# Mgmt.net
KiCad netlist of a schematic drawn in Altium Designer
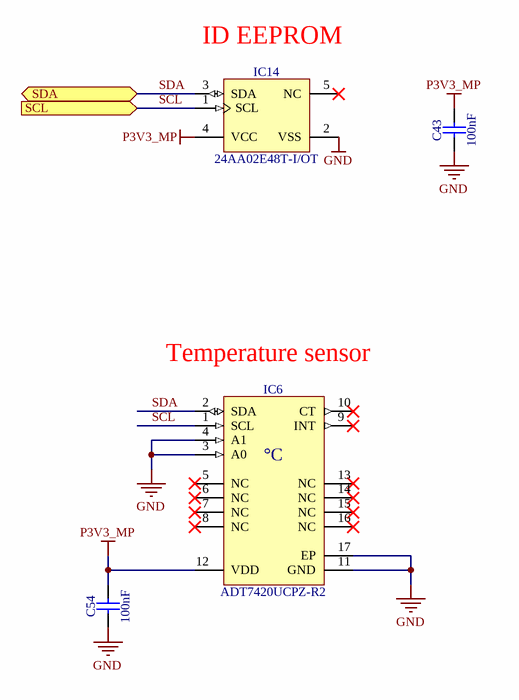
[diagram p0: Mgmt.SchDoc]

(export (version "E")
  (design (tool "Eeschema 10.0.6"))
  (components
    (comp (ref "C43")
      (value "100nF")
      (footprint "CAPC1005X55N")
      (description "Non-polarised capacitor")
      (fields
        (field (name "PART NUMBER") "CC0402_100NF_16V_10%_X5R")
        (field (name "VOLTAGE") "16V")
        (field (name "AUTHOR") "CERN DEM JLC")
      )
      (libsource (lib "Capacitors") (part "Capacitor - non polarized"))
    )
    (comp (ref "C54")
      (value "100nF")
      (footprint "CAPC1005X55N")
      (description "Non-polarised capacitor")
      (fields
        (field (name "PART NUMBER") "CC0402_100NF_16V_10%_X5R")
        (field (name "VOLTAGE") "16V")
        (field (name "AUTHOR") "CERN DEM JLC")
      )
      (libsource (lib "Capacitors") (part "Capacitor - non polarized"))
    )
    (comp (ref "IC6")
      (value "ADT7420UCPZ-R2")
      (footprint "QFN65P400X400X80-17N-S270")
      (description "±0.25°C Accurate, 16-Bit Digital I2C Temperature Sensor")
      (fields (field (name "MANUFACTURER") "ANALOG DEVICES") (field (name "AUTHOR") "CERN DEM JLC"))
      (libsource (lib "ICs And Semiconductors") (part "ADT7420"))
    )
    (comp (ref "IC14")
      (value "24AA02E48T-I/OT")
      (footprint "SOT95P280X145-5N")
      (description "1.7V-5.5V, 2K I2C Serial EEPROM With EUI-48 Node Identity")
      (fields (field (name "MANUFACTURER") "MICROCHIP TECHNOLOGY") (field (name "AUTHOR") "CERN DEM MR"))
      (libsource (lib "ICs And Semiconductors") (part "24AA02E48T-I/OT"))
    )
  )
  (nets
    (net (code "1") (name "/SCL") (class "Default")
      (node (ref "IC14") (pin "1") (pinfunction "SCL_1") (pintype "input"))
      (node (ref "IC6") (pin "1") (pinfunction "SCL_1") (pintype "input"))
    )
    (net (code "2") (name "/SDA") (class "Default")
      (node (ref "IC14") (pin "3") (pinfunction "SDA_3") (pintype "bidirectional"))
      (node (ref "IC6") (pin "2") (pinfunction "SDA_2") (pintype "bidirectional"))
    )
    (net (code "3") (name "GND") (class "Default")
      (node (ref "C43") (pin "1") (pinfunction "1_1") (pintype "passive"))
      (node (ref "C54") (pin "1") (pinfunction "1_1") (pintype "passive"))
      (node (ref "IC14") (pin "2") (pinfunction "VSS_2") (pintype "power_in"))
      (node (ref "IC6") (pin "11") (pinfunction "GND_11") (pintype "power_in"))
      (node (ref "IC6") (pin "17") (pinfunction "EP_17") (pintype "power_in"))
      (node (ref "IC6") (pin "3") (pinfunction "A0_3") (pintype "input"))
      (node (ref "IC6") (pin "4") (pinfunction "A1_4") (pintype "input"))
    )
    (net (code "4") (name "P3V3_MP") (class "Default")
      (node (ref "C43") (pin "2") (pinfunction "2_2") (pintype "passive"))
      (node (ref "C54") (pin "2") (pinfunction "2_2") (pintype "passive"))
      (node (ref "IC14") (pin "4") (pinfunction "VCC_4") (pintype "power_in"))
      (node (ref "IC6") (pin "12") (pinfunction "VDD_12") (pintype "power_in"))
    )
    (net (code "5") (name "unconnected-(IC6-CT-Pad10)") (class "Default")
      (node (ref "IC6") (pin "10") (pinfunction "CT_10") (pintype "output+no_connect"))
    )
    (net (code "6") (name "unconnected-(IC6-INT-Pad9)") (class "Default")
      (node (ref "IC6") (pin "9") (pinfunction "INT_9") (pintype "output+no_connect"))
    )
    (net (code "7") (name "unconnected-(IC6-NC-Pad5)") (class "Default")
      (node (ref "IC6") (pin "5") (pinfunction "NC_5") (pintype "passive+no_connect"))
    )
    (net (code "8") (name "unconnected-(IC6-NC-Pad6)") (class "Default")
      (node (ref "IC6") (pin "6") (pinfunction "NC_6") (pintype "passive+no_connect"))
    )
    (net (code "9") (name "unconnected-(IC6-NC-Pad7)") (class "Default")
      (node (ref "IC6") (pin "7") (pinfunction "NC_7") (pintype "passive+no_connect"))
    )
    (net (code "10") (name "unconnected-(IC6-NC-Pad8)") (class "Default")
      (node (ref "IC6") (pin "8") (pinfunction "NC_8") (pintype "passive+no_connect"))
    )
    (net (code "11") (name "unconnected-(IC6-NC-Pad13)") (class "Default")
      (node (ref "IC6") (pin "13") (pinfunction "NC_13") (pintype "passive+no_connect"))
    )
    (net (code "12") (name "unconnected-(IC6-NC-Pad14)") (class "Default")
      (node (ref "IC6") (pin "14") (pinfunction "NC_14") (pintype "passive+no_connect"))
    )
    (net (code "13") (name "unconnected-(IC6-NC-Pad15)") (class "Default")
      (node (ref "IC6") (pin "15") (pinfunction "NC_15") (pintype "passive+no_connect"))
    )
    (net (code "14") (name "unconnected-(IC6-NC-Pad16)") (class "Default")
      (node (ref "IC6") (pin "16") (pinfunction "NC_16") (pintype "passive+no_connect"))
    )
    (net (code "15") (name "unconnected-(IC14-NC-Pad5)") (class "Default")
      (node (ref "IC14") (pin "5") (pinfunction "NC_5") (pintype "passive+no_connect"))
    )
  )
)
